# DRON.net
KiCad netlist of a schematic drawn in EAGLE
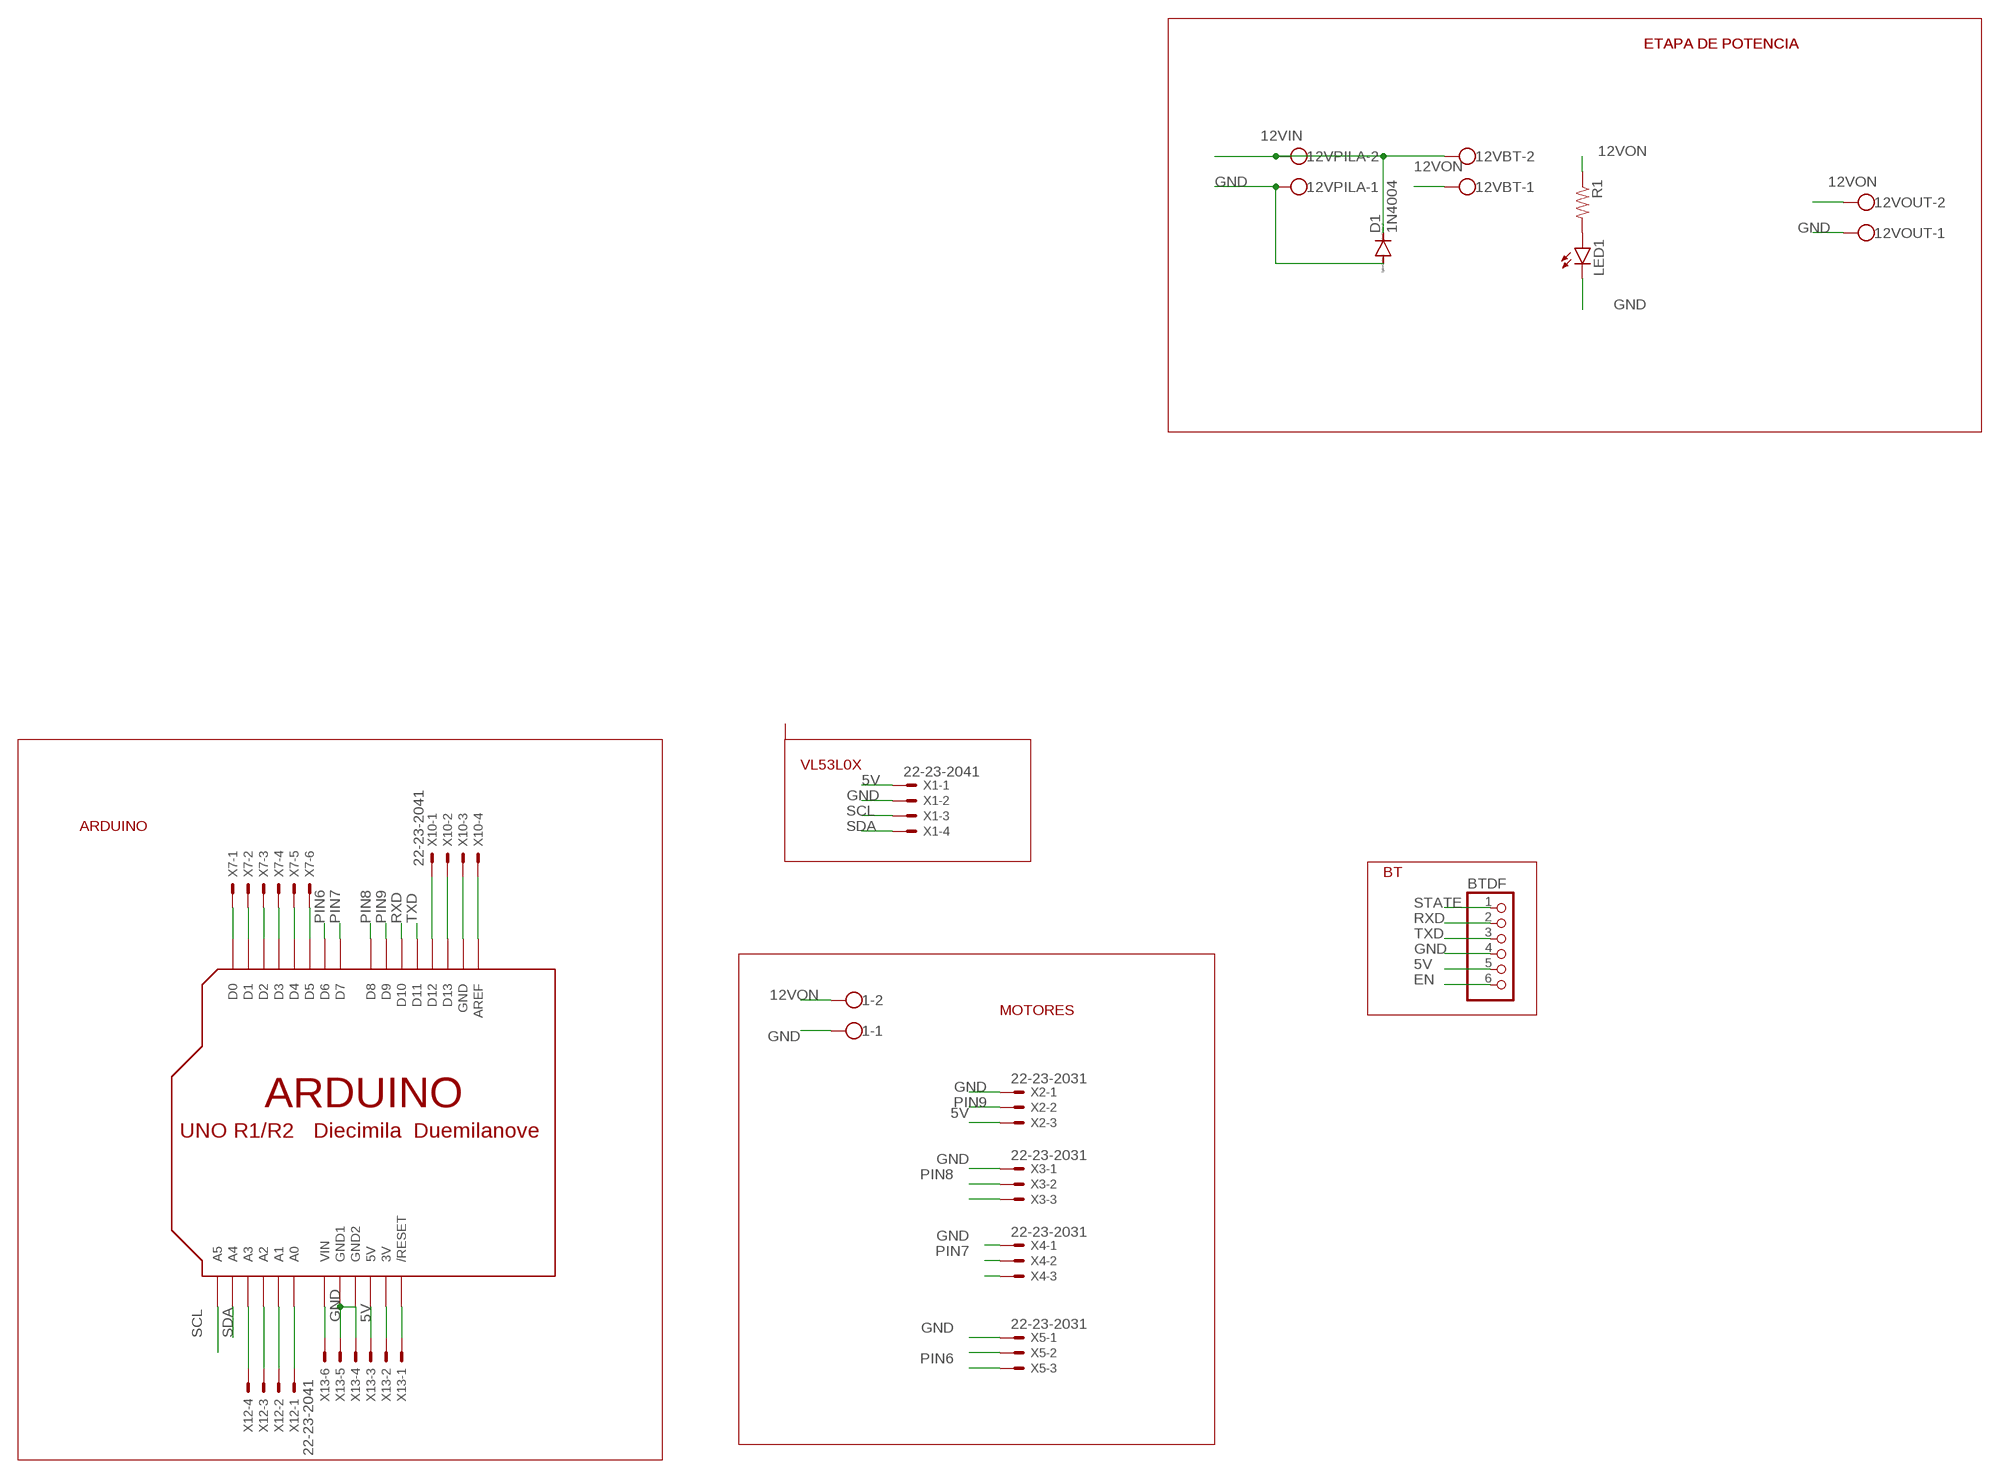
[diagram p0: schematic, sheet 1]

(export (version "E")
  (design (tool "Eeschema 10.0.6"))
  (components
    (comp (ref "1")
      (value "W237-102")
      (footprint "eagle-import:W237-102")
      (fields (field (name "MPN") "237-102"))
      (libsource (lib "eagle-import") (part "W237-102"))
    )
    (comp (ref "12VBT")
      (value "W237-102")
      (footprint "eagle-import:W237-102")
      (fields (field (name "MPN") "237-102"))
      (libsource (lib "eagle-import") (part "W237-102"))
    )
    (comp (ref "12VOUT")
      (value "W237-102")
      (footprint "eagle-import:W237-102")
      (fields (field (name "MPN") "237-102"))
      (libsource (lib "eagle-import") (part "W237-102"))
    )
    (comp (ref "12VPILA")
      (value "W237-102")
      (footprint "eagle-import:W237-102")
      (fields (field (name "MPN") "237-102"))
      (libsource (lib "eagle-import") (part "W237-102"))
    )
    (comp (ref "BTDF")
      (value "PINHD-1X6")
      (footprint "eagle-import:1X06")
      (libsource (lib "eagle-import") (part "PINHD-1X6"))
    )
    (comp (ref "D1")
      (value "1N4004")
      (footprint "eagle-import:DO41-10")
      (libsource (lib "eagle-import") (part "1N4004"))
    )
    (comp (ref "LED1")
      (value "LED5MM")
      (footprint "eagle-import:LED5MM")
      (libsource (lib "eagle-import") (part "LED5MM"))
    )
    (comp (ref "R1")
      (value "R-US_0204/7")
      (footprint "eagle-import:0204_7")
      (libsource (lib "eagle-import") (part "R-US_0204/7"))
    )
    (comp (ref "U$2")
      (value "ARDUINO-BPLACE")
      (footprint "eagle-import:ARDUINO-BPLACE")
      (libsource (lib "eagle-import") (part "ARDUINO-BPLACE"))
    )
    (comp (ref "X1")
      (value "22-23-2041")
      (footprint "eagle-import:22-23-2041")
      (fields (field (name "MF") "MOLEX"))
      (libsource (lib "eagle-import") (part "22-23-2041"))
    )
    (comp (ref "X2")
      (value "22-23-2031")
      (footprint "eagle-import:22-23-2031")
      (fields (field (name "MF") "MOLEX"))
      (libsource (lib "eagle-import") (part "22-23-2031"))
    )
    (comp (ref "X3")
      (value "22-23-2031")
      (footprint "eagle-import:22-23-2031")
      (fields (field (name "MF") "MOLEX"))
      (libsource (lib "eagle-import") (part "22-23-2031"))
    )
    (comp (ref "X4")
      (value "22-23-2031")
      (footprint "eagle-import:22-23-2031")
      (fields (field (name "MF") "MOLEX"))
      (libsource (lib "eagle-import") (part "22-23-2031"))
    )
    (comp (ref "X5")
      (value "22-23-2031")
      (footprint "eagle-import:22-23-2031")
      (fields (field (name "MF") "MOLEX"))
      (libsource (lib "eagle-import") (part "22-23-2031"))
    )
    (comp (ref "X7")
      (value "22-23-2061")
      (footprint "eagle-import:22-23-2061")
      (fields (field (name "MF") "MOLEX"))
      (libsource (lib "eagle-import") (part "22-23-2061"))
    )
    (comp (ref "X10")
      (value "22-23-2041")
      (footprint "eagle-import:22-23-2041")
      (fields (field (name "MF") "MOLEX"))
      (libsource (lib "eagle-import") (part "22-23-2041"))
    )
    (comp (ref "X12")
      (value "22-23-2041")
      (footprint "eagle-import:22-23-2041")
      (fields (field (name "MF") "MOLEX"))
      (libsource (lib "eagle-import") (part "22-23-2041"))
    )
    (comp (ref "X13")
      (value "22-23-2061")
      (footprint "eagle-import:22-23-2061")
      (fields (field (name "MF") "MOLEX"))
      (libsource (lib "eagle-import") (part "22-23-2061"))
    )
  )
  (nets
    (net (code "1") (name "/5V") (class "Default")
      (node (ref "BTDF") (pin "5") (pinfunction "5_5") (pintype "passive"))
      (node (ref "U$2") (pin "5V") (pinfunction "5V_5V") (pintype "power_in"))
      (node (ref "X1") (pin "1") (pinfunction "S_1") (pintype "passive"))
      (node (ref "X13") (pin "3") (pinfunction "S_3") (pintype "passive"))
      (node (ref "X2") (pin "3") (pinfunction "S_3") (pintype "passive"))
    )
    (net (code "2") (name "/12VIN") (class "Default")
      (node (ref "12VBT") (pin "2") (pinfunction "KL_2") (pintype "passive"))
      (node (ref "12VPILA") (pin "2") (pinfunction "KL_2") (pintype "passive"))
      (node (ref "D1") (pin "C") (pinfunction "C_C") (pintype "passive"))
    )
    (net (code "3") (name "/12VON") (class "Default")
      (node (ref "1") (pin "2") (pinfunction "KL_2") (pintype "passive"))
      (node (ref "12VBT") (pin "1") (pinfunction "KL_1") (pintype "passive"))
      (node (ref "12VOUT") (pin "2") (pinfunction "KL_2") (pintype "passive"))
      (node (ref "R1") (pin "1") (pinfunction "1_1") (pintype "passive"))
    )
    (net (code "4") (name "/EN") (class "Default")
      (node (ref "BTDF") (pin "6") (pinfunction "6_6") (pintype "passive"))
    )
    (net (code "5") (name "/GND") (class "Default")
      (node (ref "1") (pin "1") (pinfunction "KL_1") (pintype "passive"))
      (node (ref "12VOUT") (pin "1") (pinfunction "KL_1") (pintype "passive"))
      (node (ref "12VPILA") (pin "1") (pinfunction "KL_1") (pintype "passive"))
      (node (ref "BTDF") (pin "4") (pinfunction "4_4") (pintype "passive"))
      (node (ref "D1") (pin "A") (pinfunction "A_A") (pintype "passive"))
      (node (ref "LED1") (pin "K") (pinfunction "C_K") (pintype "passive"))
      (node (ref "U$2") (pin "GND1") (pinfunction "GND1_GND1") (pintype "power_in"))
      (node (ref "U$2") (pin "GND2") (pinfunction "GND2_GND2") (pintype "power_in"))
      (node (ref "X1") (pin "2") (pinfunction "S_2") (pintype "passive"))
      (node (ref "X13") (pin "4") (pinfunction "S_4") (pintype "passive"))
      (node (ref "X13") (pin "5") (pinfunction "S_5") (pintype "passive"))
      (node (ref "X2") (pin "1") (pinfunction "S_1") (pintype "passive"))
      (node (ref "X3") (pin "1") (pinfunction "S_1") (pintype "passive"))
      (node (ref "X4") (pin "1") (pinfunction "S_1") (pintype "passive"))
      (node (ref "X5") (pin "1") (pinfunction "S_1") (pintype "passive"))
    )
    (net (code "6") (name "/PIN6") (class "Default")
      (node (ref "U$2") (pin "D6") (pinfunction "D6_D6") (pintype "bidirectional"))
      (node (ref "X5") (pin "2") (pinfunction "S_2") (pintype "passive"))
    )
    (net (code "7") (name "/PIN7") (class "Default")
      (node (ref "U$2") (pin "D7") (pinfunction "D7_D7") (pintype "bidirectional"))
      (node (ref "X4") (pin "2") (pinfunction "S_2") (pintype "passive"))
    )
    (net (code "8") (name "/PIN8") (class "Default")
      (node (ref "U$2") (pin "D8") (pinfunction "D8_D8") (pintype "bidirectional"))
      (node (ref "X3") (pin "2") (pinfunction "S_2") (pintype "passive"))
    )
    (net (code "9") (name "/PIN9") (class "Default")
      (node (ref "U$2") (pin "D9") (pinfunction "D9_D9") (pintype "bidirectional"))
      (node (ref "X2") (pin "2") (pinfunction "S_2") (pintype "passive"))
    )
    (net (code "10") (name "/RXD") (class "Default")
      (node (ref "BTDF") (pin "2") (pinfunction "2_2") (pintype "passive"))
      (node (ref "U$2") (pin "D10") (pinfunction "D10_D10") (pintype "bidirectional"))
    )
    (net (code "11") (name "/SCL") (class "Default")
      (node (ref "U$2") (pin "A5") (pinfunction "A5_A5") (pintype "bidirectional"))
      (node (ref "X1") (pin "3") (pinfunction "S_3") (pintype "passive"))
    )
    (net (code "12") (name "/SDA") (class "Default")
      (node (ref "U$2") (pin "A4") (pinfunction "A4_A4") (pintype "bidirectional"))
      (node (ref "X1") (pin "4") (pinfunction "S_4") (pintype "passive"))
    )
    (net (code "13") (name "/STATE") (class "Default")
      (node (ref "BTDF") (pin "1") (pinfunction "1_1") (pintype "passive"))
    )
    (net (code "14") (name "/TXD") (class "Default")
      (node (ref "BTDF") (pin "3") (pinfunction "3_3") (pintype "passive"))
      (node (ref "U$2") (pin "D11") (pinfunction "D11_D11") (pintype "bidirectional"))
    )
    (net (code "15") (name "Net-(LED1-PadA)") (class "Default")
      (node (ref "LED1") (pin "A") (pinfunction "A_A") (pintype "passive"))
      (node (ref "R1") (pin "2") (pinfunction "2_2") (pintype "passive"))
    )
    (net (code "16") (name "Net-(U$2-{slash}RESET)") (class "Default")
      (node (ref "U$2") (pin "RESET") (pinfunction "/RESET_RESET") (pintype "bidirectional"))
      (node (ref "X13") (pin "1") (pinfunction "S_1") (pintype "passive"))
    )
    (net (code "17") (name "Net-(X7A-S)") (class "Default")
      (node (ref "U$2") (pin "D0") (pinfunction "D0_D0") (pintype "bidirectional"))
      (node (ref "X7") (pin "1") (pinfunction "S_1") (pintype "passive"))
    )
    (net (code "18") (name "Net-(X7B-S)") (class "Default")
      (node (ref "U$2") (pin "D1") (pinfunction "D1_D1") (pintype "bidirectional"))
      (node (ref "X7") (pin "2") (pinfunction "S_2") (pintype "passive"))
    )
    (net (code "19") (name "Net-(X7C-S)") (class "Default")
      (node (ref "U$2") (pin "D2") (pinfunction "D2_D2") (pintype "bidirectional"))
      (node (ref "X7") (pin "3") (pinfunction "S_3") (pintype "passive"))
    )
    (net (code "20") (name "Net-(X7D-S)") (class "Default")
      (node (ref "U$2") (pin "D3") (pinfunction "D3_D3") (pintype "bidirectional"))
      (node (ref "X7") (pin "4") (pinfunction "S_4") (pintype "passive"))
    )
    (net (code "21") (name "Net-(X7E-S)") (class "Default")
      (node (ref "U$2") (pin "D4") (pinfunction "D4_D4") (pintype "bidirectional"))
      (node (ref "X7") (pin "5") (pinfunction "S_5") (pintype "passive"))
    )
    (net (code "22") (name "Net-(X7F-S)") (class "Default")
      (node (ref "U$2") (pin "D5") (pinfunction "D5_D5") (pintype "bidirectional"))
      (node (ref "X7") (pin "6") (pinfunction "S_6") (pintype "passive"))
    )
    (net (code "23") (name "Net-(X10A-S)") (class "Default")
      (node (ref "U$2") (pin "D12") (pinfunction "D12_D12") (pintype "bidirectional"))
      (node (ref "X10") (pin "1") (pinfunction "S_1") (pintype "passive"))
    )
    (net (code "24") (name "Net-(X10B-S)") (class "Default")
      (node (ref "U$2") (pin "D13") (pinfunction "D13_D13") (pintype "bidirectional"))
      (node (ref "X10") (pin "2") (pinfunction "S_2") (pintype "passive"))
    )
    (net (code "25") (name "Net-(X10C-S)") (class "Default")
      (node (ref "U$2") (pin "GND") (pinfunction "GND_GND") (pintype "power_in"))
      (node (ref "X10") (pin "3") (pinfunction "S_3") (pintype "passive"))
    )
    (net (code "26") (name "Net-(X10D-S)") (class "Default")
      (node (ref "U$2") (pin "AREF") (pinfunction "AREF_AREF") (pintype "bidirectional"))
      (node (ref "X10") (pin "4") (pinfunction "S_4") (pintype "passive"))
    )
    (net (code "27") (name "Net-(X12A-S)") (class "Default")
      (node (ref "U$2") (pin "A0") (pinfunction "A0_A0") (pintype "bidirectional"))
      (node (ref "X12") (pin "1") (pinfunction "S_1") (pintype "passive"))
    )
    (net (code "28") (name "Net-(X12B-S)") (class "Default")
      (node (ref "U$2") (pin "A1") (pinfunction "A1_A1") (pintype "bidirectional"))
      (node (ref "X12") (pin "2") (pinfunction "S_2") (pintype "passive"))
    )
    (net (code "29") (name "Net-(X12C-S)") (class "Default")
      (node (ref "U$2") (pin "A2") (pinfunction "A2_A2") (pintype "bidirectional"))
      (node (ref "X12") (pin "3") (pinfunction "S_3") (pintype "passive"))
    )
    (net (code "30") (name "Net-(X12D-S)") (class "Default")
      (node (ref "U$2") (pin "A3") (pinfunction "A3_A3") (pintype "bidirectional"))
      (node (ref "X12") (pin "4") (pinfunction "S_4") (pintype "passive"))
    )
    (net (code "31") (name "Net-(X13B-S)") (class "Default")
      (node (ref "U$2") (pin "3V") (pinfunction "3V_3V") (pintype "power_in"))
      (node (ref "X13") (pin "2") (pinfunction "S_2") (pintype "passive"))
    )
    (net (code "32") (name "Net-(X13F-S)") (class "Default")
      (node (ref "U$2") (pin "VIN") (pinfunction "VIN_VIN") (pintype "power_in"))
      (node (ref "X13") (pin "6") (pinfunction "S_6") (pintype "passive"))
    )
    (net (code "33") (name "unconnected-(X3C-S-Pad3)") (class "Default")
      (node (ref "X3") (pin "3") (pinfunction "S_3") (pintype "passive"))
    )
    (net (code "34") (name "unconnected-(X4C-S-Pad3)") (class "Default")
      (node (ref "X4") (pin "3") (pinfunction "S_3") (pintype "passive"))
    )
    (net (code "35") (name "unconnected-(X5C-S-Pad3)") (class "Default")
      (node (ref "X5") (pin "3") (pinfunction "S_3") (pintype "passive"))
    )
  )
)
